# antenna-bottomside.net
KiCad netlist of a schematic drawn in Altium Designer
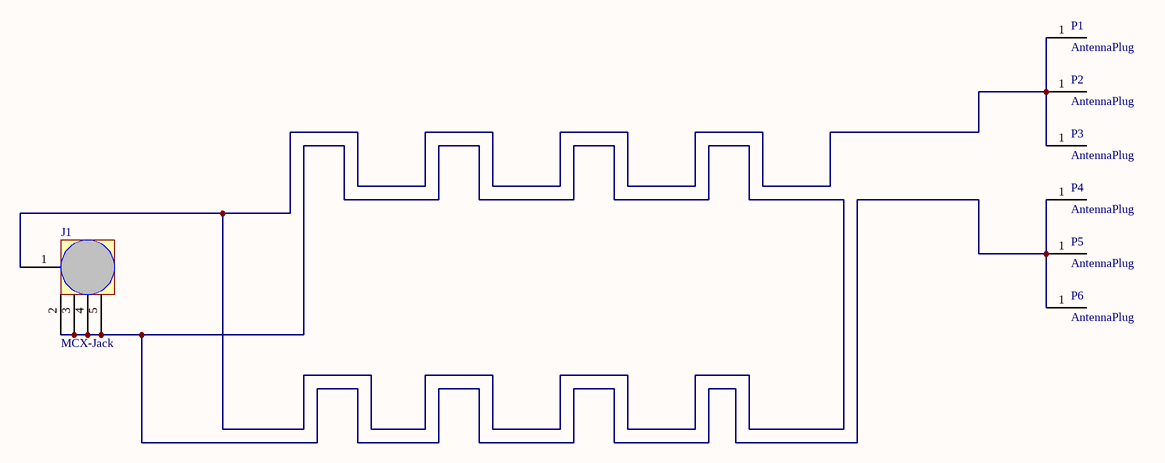
[diagram p0: antenna-bottomside.SchDoc]

(export (version "E")
  (design (tool "Eeschema 10.0.6"))
  (components
    (comp (ref "J1") (value "MCX-Jack") (footprint "MCX-Jack") (libsource (lib "urover") (part "MCX-Jack")))
    (comp (ref "P1")
      (value "AntennaPlug")
      (footprint "Keystone_PN8737")
      (libsource (lib "urover") (part "AntennaPlug"))
    )
    (comp (ref "P2")
      (value "AntennaPlug")
      (footprint "Keystone_PN8737")
      (libsource (lib "urover") (part "AntennaPlug"))
    )
    (comp (ref "P3")
      (value "AntennaPlug")
      (footprint "Keystone_PN8737")
      (libsource (lib "urover") (part "AntennaPlug"))
    )
    (comp (ref "P4")
      (value "AntennaPlug")
      (footprint "Keystone_PN8737")
      (libsource (lib "urover") (part "AntennaPlug"))
    )
    (comp (ref "P5")
      (value "AntennaPlug")
      (footprint "Keystone_PN8737")
      (libsource (lib "urover") (part "AntennaPlug"))
    )
    (comp (ref "P6")
      (value "AntennaPlug")
      (footprint "Keystone_PN8737")
      (libsource (lib "urover") (part "AntennaPlug"))
    )
  )
  (nets
    (net (code "1") (name "Net-(J1-Pad1)") (class "Default")
      (node (ref "J1") (pin "1") (pintype "passive"))
      (node (ref "J1") (pin "2") (pintype "passive"))
      (node (ref "J1") (pin "3") (pintype "passive"))
      (node (ref "J1") (pin "4") (pintype "passive"))
      (node (ref "J1") (pin "5") (pintype "passive"))
    )
    (net (code "2") (name "unconnected-(P1-Pad1)") (class "Default")
      (node (ref "P1") (pin "1") (pinfunction "1_1") (pintype "passive"))
    )
    (net (code "3") (name "unconnected-(P2-Pad1)") (class "Default")
      (node (ref "P2") (pin "1") (pinfunction "1_1") (pintype "passive"))
    )
    (net (code "4") (name "unconnected-(P3-Pad1)") (class "Default")
      (node (ref "P3") (pin "1") (pinfunction "1_1") (pintype "passive"))
    )
    (net (code "5") (name "unconnected-(P4-Pad1)") (class "Default")
      (node (ref "P4") (pin "1") (pinfunction "1_1") (pintype "passive"))
    )
    (net (code "6") (name "unconnected-(P5-Pad1)") (class "Default")
      (node (ref "P5") (pin "1") (pinfunction "1_1") (pintype "passive"))
    )
    (net (code "7") (name "unconnected-(P6-Pad1)") (class "Default")
      (node (ref "P6") (pin "1") (pinfunction "1_1") (pintype "passive"))
    )
  )
)
